# atmega1284_tactile2.net
KiCad netlist of a schematic drawn in EAGLE
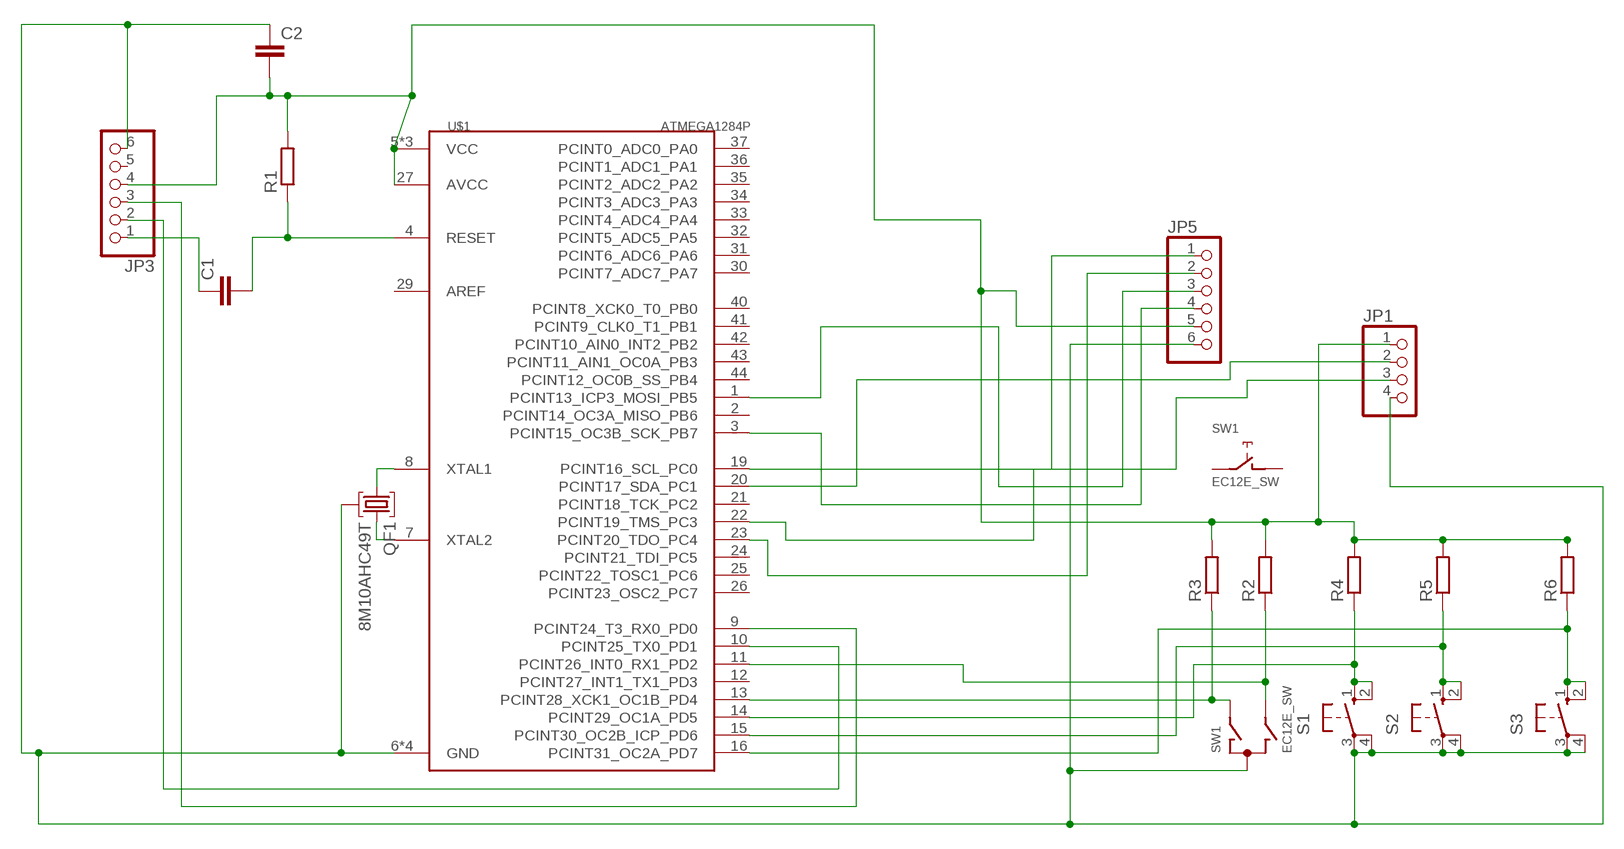
[diagram p0: schematic, sheet 1]

(export (version "E")
  (design (tool "Eeschema 10.0.6"))
  (components
    (comp (ref "C1")
      (value "C-EUC0805")
      (footprint "eagle-import:C0805")
      (libsource (lib "eagle-import") (part "C-EUC0805"))
    )
    (comp (ref "C2")
      (value "C-EUC0805")
      (footprint "eagle-import:C0805")
      (libsource (lib "eagle-import") (part "C-EUC0805"))
    )
    (comp (ref "JP1")
      (value "PINHD-1X4")
      (footprint "eagle-import:1X04")
      (libsource (lib "eagle-import") (part "PINHD-1X4"))
    )
    (comp (ref "JP3")
      (value "PINHD-1X6")
      (footprint "eagle-import:1X06")
      (libsource (lib "eagle-import") (part "PINHD-1X6"))
    )
    (comp (ref "JP5")
      (value "PINHD-1X6")
      (footprint "eagle-import:1X06")
      (libsource (lib "eagle-import") (part "PINHD-1X6"))
    )
    (comp (ref "QF1")
      (value "8M10AHC49T")
      (footprint "eagle-import:HC49U")
      (libsource (lib "eagle-import") (part "8M10AHC49T"))
    )
    (comp (ref "R1")
      (value "R-EU_R0805")
      (footprint "eagle-import:R0805")
      (libsource (lib "eagle-import") (part "R-EU_R0805"))
    )
    (comp (ref "R2")
      (value "R-EU_R0805")
      (footprint "eagle-import:R0805")
      (libsource (lib "eagle-import") (part "R-EU_R0805"))
    )
    (comp (ref "R3")
      (value "R-EU_R0805")
      (footprint "eagle-import:R0805")
      (libsource (lib "eagle-import") (part "R-EU_R0805"))
    )
    (comp (ref "R4")
      (value "R-EU_R0805")
      (footprint "eagle-import:R0805")
      (libsource (lib "eagle-import") (part "R-EU_R0805"))
    )
    (comp (ref "R5")
      (value "R-EU_R0805")
      (footprint "eagle-import:R0805")
      (libsource (lib "eagle-import") (part "R-EU_R0805"))
    )
    (comp (ref "R6")
      (value "R-EU_R0805")
      (footprint "eagle-import:R0805")
      (libsource (lib "eagle-import") (part "R-EU_R0805"))
    )
    (comp (ref "S1")
      (value "10-XX")
      (footprint "eagle-import:B3F-10XX")
      (fields (field (name "MPN") "B3F-1000"))
      (libsource (lib "eagle-import") (part "10-XX"))
    )
    (comp (ref "S2")
      (value "10-XX")
      (footprint "eagle-import:B3F-10XX")
      (fields (field (name "MPN") "B3F-1000"))
      (libsource (lib "eagle-import") (part "10-XX"))
    )
    (comp (ref "S3")
      (value "10-XX")
      (footprint "eagle-import:B3F-10XX")
      (fields (field (name "MPN") "B3F-1000"))
      (libsource (lib "eagle-import") (part "10-XX"))
    )
    (comp (ref "SW1")
      (value "EC12E_SW")
      (footprint "eagle-import:ALPS_EC12E_SW")
      (fields (field (name "MPN") "EC12E2424407"))
      (libsource (lib "eagle-import") (part "EC12E_SW"))
    )
    (comp (ref "U$1")
      (value "ATMEGA1284P")
      (footprint "eagle-import:TQFP44")
      (libsource (lib "eagle-import") (part "ATMEGA1284P"))
    )
  )
  (nets
    (net (code "1") (name "Net-(C1-Pad1)") (class "Default")
      (node (ref "C1") (pin "1") (pinfunction "1_1") (pintype "passive"))
      (node (ref "JP3") (pin "1") (pinfunction "1_1") (pintype "passive"))
    )
    (net (code "2") (name "Net-(S1-P)") (class "Default")
      (node (ref "C2") (pin "1") (pinfunction "1_1") (pintype "passive"))
      (node (ref "JP1") (pin "4") (pinfunction "4_4") (pintype "passive"))
      (node (ref "JP3") (pin "6") (pinfunction "6_6") (pintype "passive"))
      (node (ref "JP5") (pin "6") (pinfunction "6_6") (pintype "passive"))
      (node (ref "QF1") (pin "2") (pinfunction "2_2") (pintype "passive"))
      (node (ref "S1") (pin "3") (pinfunction "P_3") (pintype "passive"))
      (node (ref "S1") (pin "4") (pinfunction "P1_4") (pintype "passive"))
      (node (ref "S2") (pin "3") (pinfunction "P_3") (pintype "passive"))
      (node (ref "S2") (pin "4") (pinfunction "P1_4") (pintype "passive"))
      (node (ref "S3") (pin "3") (pinfunction "P_3") (pintype "passive"))
      (node (ref "S3") (pin "4") (pinfunction "P1_4") (pintype "passive"))
      (node (ref "SW1") (pin "C") (pinfunction "C_C") (pintype "passive"))
      (node (ref "U$1") (pin "18") (pinfunction "GND_18") (pintype "bidirectional"))
      (node (ref "U$1") (pin "28") (pinfunction "GND_28") (pintype "bidirectional"))
      (node (ref "U$1") (pin "39") (pinfunction "GND_39") (pintype "bidirectional"))
      (node (ref "U$1") (pin "6") (pinfunction "GND_6") (pintype "bidirectional"))
    )
    (net (code "3") (name "Net-(S1-S)") (class "Default")
      (node (ref "R4") (pin "1") (pinfunction "1_1") (pintype "passive"))
      (node (ref "S1") (pin "1") (pinfunction "S_1") (pintype "passive"))
      (node (ref "S1") (pin "2") (pinfunction "S1_2") (pintype "passive"))
      (node (ref "U$1") (pin "14") (pinfunction "PCINT29_OC1A_PD5_14") (pintype "bidirectional"))
    )
    (net (code "4") (name "Net-(S2-S)") (class "Default")
      (node (ref "R5") (pin "1") (pinfunction "1_1") (pintype "passive"))
      (node (ref "S2") (pin "1") (pinfunction "S_1") (pintype "passive"))
      (node (ref "S2") (pin "2") (pinfunction "S1_2") (pintype "passive"))
      (node (ref "U$1") (pin "15") (pinfunction "PCINT30_OC2B_ICP_PD6_15") (pintype "bidirectional"))
    )
    (net (code "5") (name "Net-(S3-S)") (class "Default")
      (node (ref "R6") (pin "1") (pinfunction "1_1") (pintype "passive"))
      (node (ref "S3") (pin "1") (pinfunction "S_1") (pintype "passive"))
      (node (ref "S3") (pin "2") (pinfunction "S1_2") (pintype "passive"))
      (node (ref "U$1") (pin "16") (pinfunction "PCINT31_OC2A_PD7_16") (pintype "bidirectional"))
    )
    (net (code "6") (name "Net-(U$1-AVCC)") (class "Default")
      (node (ref "C2") (pin "2") (pinfunction "2_2") (pintype "passive"))
      (node (ref "JP1") (pin "1") (pinfunction "1_1") (pintype "passive"))
      (node (ref "JP3") (pin "4") (pinfunction "4_4") (pintype "passive"))
      (node (ref "JP5") (pin "5") (pinfunction "5_5") (pintype "passive"))
      (node (ref "R1") (pin "2") (pinfunction "2_2") (pintype "passive"))
      (node (ref "R2") (pin "2") (pinfunction "2_2") (pintype "passive"))
      (node (ref "R3") (pin "2") (pinfunction "2_2") (pintype "passive"))
      (node (ref "R4") (pin "2") (pinfunction "2_2") (pintype "passive"))
      (node (ref "R5") (pin "2") (pinfunction "2_2") (pintype "passive"))
      (node (ref "R6") (pin "2") (pinfunction "2_2") (pintype "passive"))
      (node (ref "U$1") (pin "17") (pinfunction "VCC_17") (pintype "bidirectional"))
      (node (ref "U$1") (pin "27") (pinfunction "AVCC_27") (pintype "bidirectional"))
      (node (ref "U$1") (pin "38") (pinfunction "VCC_38") (pintype "bidirectional"))
      (node (ref "U$1") (pin "5") (pinfunction "VCC_5") (pintype "bidirectional"))
    )
    (net (code "7") (name "Net-(U$1-PCINT13_ICP3_MOSI_PB5)") (class "Default")
      (node (ref "JP5") (pin "3") (pinfunction "3_3") (pintype "passive"))
      (node (ref "U$1") (pin "1") (pinfunction "PCINT13_ICP3_MOSI_PB5_1") (pintype "bidirectional"))
    )
    (net (code "8") (name "Net-(U$1-PCINT15_OC3B_SCK_PB7)") (class "Default")
      (node (ref "JP5") (pin "4") (pinfunction "4_4") (pintype "passive"))
      (node (ref "U$1") (pin "3") (pinfunction "PCINT15_OC3B_SCK_PB7_3") (pintype "bidirectional"))
    )
    (net (code "9") (name "Net-(U$1-PCINT16_SCL_PC0)") (class "Default")
      (node (ref "JP1") (pin "3") (pinfunction "3_3") (pintype "passive"))
      (node (ref "U$1") (pin "19") (pinfunction "PCINT16_SCL_PC0_19") (pintype "bidirectional"))
    )
    (net (code "10") (name "Net-(U$1-PCINT17_SDA_PC1)") (class "Default")
      (node (ref "JP1") (pin "2") (pinfunction "2_2") (pintype "passive"))
      (node (ref "U$1") (pin "20") (pinfunction "PCINT17_SDA_PC1_20") (pintype "bidirectional"))
    )
    (net (code "11") (name "Net-(U$1-PCINT19_TMS_PC3)") (class "Default")
      (node (ref "JP5") (pin "1") (pinfunction "1_1") (pintype "passive"))
      (node (ref "U$1") (pin "22") (pinfunction "PCINT19_TMS_PC3_22") (pintype "bidirectional"))
    )
    (net (code "12") (name "Net-(U$1-PCINT20_TDO_PC4)") (class "Default")
      (node (ref "JP5") (pin "2") (pinfunction "2_2") (pintype "passive"))
      (node (ref "U$1") (pin "23") (pinfunction "PCINT20_TDO_PC4_23") (pintype "bidirectional"))
    )
    (net (code "13") (name "Net-(U$1-PCINT24_T3_RX0_PD0)") (class "Default")
      (node (ref "JP3") (pin "3") (pinfunction "3_3") (pintype "passive"))
      (node (ref "U$1") (pin "9") (pinfunction "PCINT24_T3_RX0_PD0_9") (pintype "bidirectional"))
    )
    (net (code "14") (name "Net-(U$1-PCINT25_TX0_PD1)") (class "Default")
      (node (ref "JP3") (pin "2") (pinfunction "2_2") (pintype "passive"))
      (node (ref "U$1") (pin "10") (pinfunction "PCINT25_TX0_PD1_10") (pintype "bidirectional"))
    )
    (net (code "15") (name "Net-(U$1-PCINT26_INT0_RX1_PD2)") (class "Default")
      (node (ref "R2") (pin "1") (pinfunction "1_1") (pintype "passive"))
      (node (ref "SW1") (pin "B") (pinfunction "B_B") (pintype "passive"))
      (node (ref "U$1") (pin "11") (pinfunction "PCINT26_INT0_RX1_PD2_11") (pintype "bidirectional"))
    )
    (net (code "16") (name "Net-(U$1-PCINT28_XCK1_OC1B_PD4)") (class "Default")
      (node (ref "R3") (pin "1") (pinfunction "1_1") (pintype "passive"))
      (node (ref "SW1") (pin "A") (pinfunction "A_A") (pintype "passive"))
      (node (ref "U$1") (pin "13") (pinfunction "PCINT28_XCK1_OC1B_PD4_13") (pintype "bidirectional"))
    )
    (net (code "17") (name "Net-(U$1-RESET)") (class "Default")
      (node (ref "C1") (pin "2") (pinfunction "2_2") (pintype "passive"))
      (node (ref "R1") (pin "1") (pinfunction "1_1") (pintype "passive"))
      (node (ref "U$1") (pin "4") (pinfunction "RESET_4") (pintype "bidirectional"))
    )
    (net (code "18") (name "Net-(U$1-XTAL1)") (class "Default")
      (node (ref "QF1") (pin "1") (pinfunction "1_1") (pintype "passive"))
      (node (ref "U$1") (pin "8") (pinfunction "XTAL1_8") (pintype "bidirectional"))
    )
    (net (code "19") (name "Net-(U$1-XTAL2)") (class "Default")
      (node (ref "QF1") (pin "3") (pinfunction "3_3") (pintype "passive"))
      (node (ref "U$1") (pin "7") (pinfunction "XTAL2_7") (pintype "bidirectional"))
    )
    (net (code "20") (name "unconnected-(JP3-Pad5)") (class "Default")
      (node (ref "JP3") (pin "5") (pinfunction "5_5") (pintype "passive"))
    )
    (net (code "21") (name "unconnected-(SW1B-1-PadD)") (class "Default")
      (node (ref "SW1") (pin "D") (pinfunction "1_D") (pintype "passive"))
    )
    (net (code "22") (name "unconnected-(SW1B-2-PadE)") (class "Default")
      (node (ref "SW1") (pin "E") (pinfunction "2_E") (pintype "passive"))
    )
    (net (code "23") (name "unconnected-(U$1-AREF-Pad29)") (class "Default")
      (node (ref "U$1") (pin "29") (pinfunction "AREF_29") (pintype "bidirectional"))
    )
    (net (code "24") (name "unconnected-(U$1-PCINT0_ADC0_PA0-Pad37)") (class "Default")
      (node (ref "U$1") (pin "37") (pinfunction "PCINT0_ADC0_PA0_37") (pintype "bidirectional"))
    )
    (net (code "25") (name "unconnected-(U$1-PCINT1_ADC1_PA1-Pad36)") (class "Default")
      (node (ref "U$1") (pin "36") (pinfunction "PCINT1_ADC1_PA1_36") (pintype "bidirectional"))
    )
    (net (code "26") (name "unconnected-(U$1-PCINT2_ADC2_PA2-Pad35)") (class "Default")
      (node (ref "U$1") (pin "35") (pinfunction "PCINT2_ADC2_PA2_35") (pintype "bidirectional"))
    )
    (net (code "27") (name "unconnected-(U$1-PCINT3_ADC3_PA3-Pad34)") (class "Default")
      (node (ref "U$1") (pin "34") (pinfunction "PCINT3_ADC3_PA3_34") (pintype "bidirectional"))
    )
    (net (code "28") (name "unconnected-(U$1-PCINT4_ADC4_PA4-Pad33)") (class "Default")
      (node (ref "U$1") (pin "33") (pinfunction "PCINT4_ADC4_PA4_33") (pintype "bidirectional"))
    )
    (net (code "29") (name "unconnected-(U$1-PCINT5_ADC5_PA5-Pad32)") (class "Default")
      (node (ref "U$1") (pin "32") (pinfunction "PCINT5_ADC5_PA5_32") (pintype "bidirectional"))
    )
    (net (code "30") (name "unconnected-(U$1-PCINT6_ADC6_PA6-Pad31)") (class "Default")
      (node (ref "U$1") (pin "31") (pinfunction "PCINT6_ADC6_PA6_31") (pintype "bidirectional"))
    )
    (net (code "31") (name "unconnected-(U$1-PCINT7_ADC7_PA7-Pad30)") (class "Default")
      (node (ref "U$1") (pin "30") (pinfunction "PCINT7_ADC7_PA7_30") (pintype "bidirectional"))
    )
    (net (code "32") (name "unconnected-(U$1-PCINT8_XCK0_T0_PB0-Pad40)") (class "Default")
      (node (ref "U$1") (pin "40") (pinfunction "PCINT8_XCK0_T0_PB0_40") (pintype "bidirectional"))
    )
    (net (code "33") (name "unconnected-(U$1-PCINT9_CLK0_T1_PB1-Pad41)") (class "Default")
      (node (ref "U$1") (pin "41") (pinfunction "PCINT9_CLK0_T1_PB1_41") (pintype "bidirectional"))
    )
    (net (code "34") (name "unconnected-(U$1-PCINT10_AIN0_INT2_PB2-Pad42)") (class "Default")
      (node (ref "U$1") (pin "42") (pinfunction "PCINT10_AIN0_INT2_PB2_42") (pintype "bidirectional"))
    )
    (net (code "35") (name "unconnected-(U$1-PCINT11_AIN1_OC0A_PB3-Pad43)") (class "Default")
      (node (ref "U$1") (pin "43") (pinfunction "PCINT11_AIN1_OC0A_PB3_43") (pintype "bidirectional"))
    )
    (net (code "36") (name "unconnected-(U$1-PCINT12_OC0B_SS_PB4-Pad44)") (class "Default")
      (node (ref "U$1") (pin "44") (pinfunction "PCINT12_OC0B_SS_PB4_44") (pintype "bidirectional"))
    )
    (net (code "37") (name "unconnected-(U$1-PCINT14_OC3A_MISO_PB6-Pad2)") (class "Default")
      (node (ref "U$1") (pin "2") (pinfunction "PCINT14_OC3A_MISO_PB6_2") (pintype "bidirectional"))
    )
    (net (code "38") (name "unconnected-(U$1-PCINT18_TCK_PC2-Pad21)") (class "Default")
      (node (ref "U$1") (pin "21") (pinfunction "PCINT18_TCK_PC2_21") (pintype "bidirectional"))
    )
    (net (code "39") (name "unconnected-(U$1-PCINT21_TDI_PC5-Pad24)") (class "Default")
      (node (ref "U$1") (pin "24") (pinfunction "PCINT21_TDI_PC5_24") (pintype "bidirectional"))
    )
    (net (code "40") (name "unconnected-(U$1-PCINT22_TOSC1_PC6-Pad25)") (class "Default")
      (node (ref "U$1") (pin "25") (pinfunction "PCINT22_TOSC1_PC6_25") (pintype "bidirectional"))
    )
    (net (code "41") (name "unconnected-(U$1-PCINT23_OSC2_PC7-Pad26)") (class "Default")
      (node (ref "U$1") (pin "26") (pinfunction "PCINT23_OSC2_PC7_26") (pintype "bidirectional"))
    )
    (net (code "42") (name "unconnected-(U$1-PCINT27_INT1_TX1_PD3-Pad12)") (class "Default")
      (node (ref "U$1") (pin "12") (pinfunction "PCINT27_INT1_TX1_PD3_12") (pintype "bidirectional"))
    )
  )
)
